# 2_bootleg-alps-matrix.net
KiCad netlist of a schematic drawn in Altium Designer
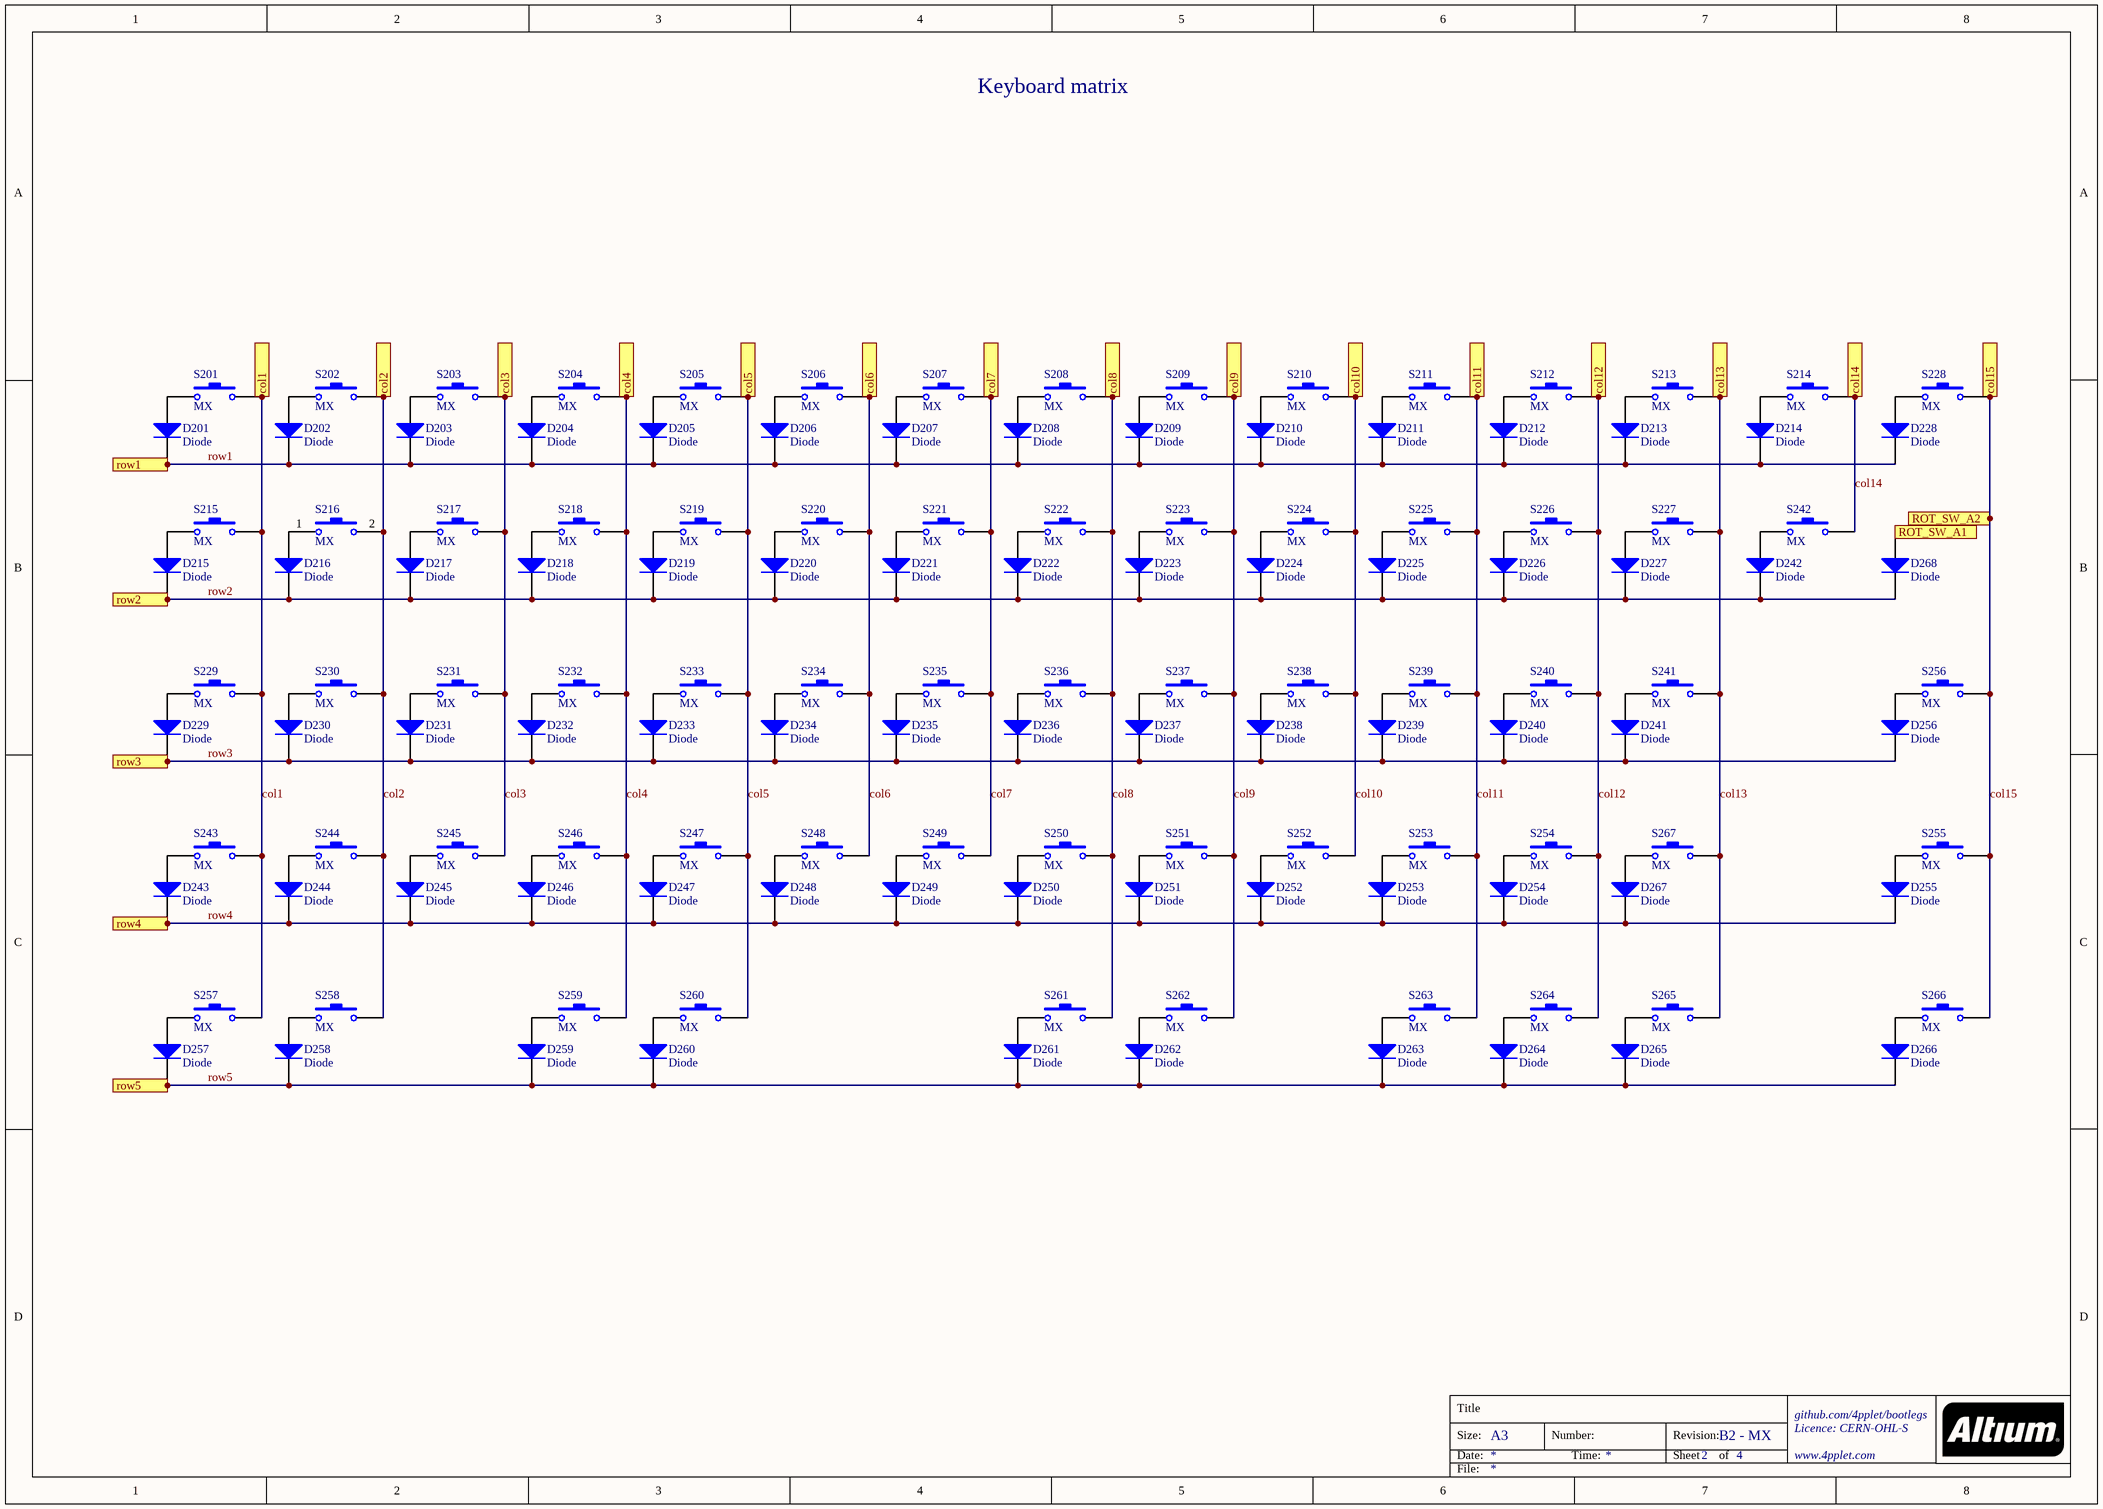
[diagram p0: 2_bootleg-alps-matrix.SchDoc]

(export (version "E")
  (design (tool "Eeschema 10.0.6"))
  (components
    (comp (ref "D201")
      (value "Diode")
      (footprint "SOD-123")
      (description "Default Diode")
      (fields (field (name "LCSC PART #") "C81598") (field (name "MRF.PART") "1N4148W"))
      (libsource (lib "Miscellaneous Devices") (part "Diode"))
    )
    (comp (ref "D202")
      (value "Diode")
      (footprint "SOD-123")
      (description "Default Diode")
      (fields (field (name "LCSC PART #") "C81598") (field (name "MRF.PART") "1N4148W"))
      (libsource (lib "Miscellaneous Devices") (part "Diode"))
    )
    (comp (ref "D203")
      (value "Diode")
      (footprint "SOD-123")
      (description "Default Diode")
      (fields (field (name "LCSC PART #") "C81598") (field (name "MRF.PART") "1N4148W"))
      (libsource (lib "Miscellaneous Devices") (part "Diode"))
    )
    (comp (ref "D204")
      (value "Diode")
      (footprint "SOD-123")
      (description "Default Diode")
      (fields (field (name "LCSC PART #") "C81598") (field (name "MRF.PART") "1N4148W"))
      (libsource (lib "Miscellaneous Devices") (part "Diode"))
    )
    (comp (ref "D205")
      (value "Diode")
      (footprint "SOD-123")
      (description "Default Diode")
      (fields (field (name "LCSC PART #") "C81598") (field (name "MRF.PART") "1N4148W"))
      (libsource (lib "Miscellaneous Devices") (part "Diode"))
    )
    (comp (ref "D206")
      (value "Diode")
      (footprint "SOD-123")
      (description "Default Diode")
      (fields (field (name "LCSC PART #") "C81598") (field (name "MRF.PART") "1N4148W"))
      (libsource (lib "Miscellaneous Devices") (part "Diode"))
    )
    (comp (ref "D207")
      (value "Diode")
      (footprint "SOD-123")
      (description "Default Diode")
      (fields (field (name "LCSC PART #") "C81598") (field (name "MRF.PART") "1N4148W"))
      (libsource (lib "Miscellaneous Devices") (part "Diode"))
    )
    (comp (ref "D208")
      (value "Diode")
      (footprint "SOD-123")
      (description "Default Diode")
      (fields (field (name "LCSC PART #") "C81598") (field (name "MRF.PART") "1N4148W"))
      (libsource (lib "Miscellaneous Devices") (part "Diode"))
    )
    (comp (ref "D209")
      (value "Diode")
      (footprint "SOD-123")
      (description "Default Diode")
      (fields (field (name "LCSC PART #") "C81598") (field (name "MRF.PART") "1N4148W"))
      (libsource (lib "Miscellaneous Devices") (part "Diode"))
    )
    (comp (ref "D210")
      (value "Diode")
      (footprint "SOD-123")
      (description "Default Diode")
      (fields (field (name "LCSC PART #") "C81598") (field (name "MRF.PART") "1N4148W"))
      (libsource (lib "Miscellaneous Devices") (part "Diode"))
    )
    (comp (ref "D211")
      (value "Diode")
      (footprint "SOD-123")
      (description "Default Diode")
      (fields (field (name "LCSC PART #") "C81598") (field (name "MRF.PART") "1N4148W"))
      (libsource (lib "Miscellaneous Devices") (part "Diode"))
    )
    (comp (ref "D212")
      (value "Diode")
      (footprint "SOD-123")
      (description "Default Diode")
      (fields (field (name "LCSC PART #") "C81598") (field (name "MRF.PART") "1N4148W"))
      (libsource (lib "Miscellaneous Devices") (part "Diode"))
    )
    (comp (ref "D213")
      (value "Diode")
      (footprint "SOD-123")
      (description "Default Diode")
      (fields (field (name "LCSC PART #") "C81598") (field (name "MRF.PART") "1N4148W"))
      (libsource (lib "Miscellaneous Devices") (part "Diode"))
    )
    (comp (ref "D214")
      (value "Diode")
      (footprint "SOD-123")
      (description "Default Diode")
      (fields (field (name "LCSC PART #") "C81598") (field (name "MRF.PART") "1N4148W"))
      (libsource (lib "Miscellaneous Devices") (part "Diode"))
    )
    (comp (ref "D215")
      (value "Diode")
      (footprint "SOD-123")
      (description "Default Diode")
      (fields (field (name "LCSC PART #") "C81598") (field (name "MRF.PART") "1N4148W"))
      (libsource (lib "Miscellaneous Devices") (part "Diode"))
    )
    (comp (ref "D216")
      (value "Diode")
      (footprint "SOD-123")
      (description "Default Diode")
      (fields (field (name "LCSC PART #") "C81598") (field (name "MRF.PART") "1N4148W"))
      (libsource (lib "Miscellaneous Devices") (part "Diode"))
    )
    (comp (ref "D217")
      (value "Diode")
      (footprint "SOD-123")
      (description "Default Diode")
      (fields (field (name "LCSC PART #") "C81598") (field (name "MRF.PART") "1N4148W"))
      (libsource (lib "Miscellaneous Devices") (part "Diode"))
    )
    (comp (ref "D218")
      (value "Diode")
      (footprint "SOD-123")
      (description "Default Diode")
      (fields (field (name "LCSC PART #") "C81598") (field (name "MRF.PART") "1N4148W"))
      (libsource (lib "Miscellaneous Devices") (part "Diode"))
    )
    (comp (ref "D219")
      (value "Diode")
      (footprint "SOD-123")
      (description "Default Diode")
      (fields (field (name "LCSC PART #") "C81598") (field (name "MRF.PART") "1N4148W"))
      (libsource (lib "Miscellaneous Devices") (part "Diode"))
    )
    (comp (ref "D220")
      (value "Diode")
      (footprint "SOD-123")
      (description "Default Diode")
      (fields (field (name "LCSC PART #") "C81598") (field (name "MRF.PART") "1N4148W"))
      (libsource (lib "Miscellaneous Devices") (part "Diode"))
    )
    (comp (ref "D221")
      (value "Diode")
      (footprint "SOD-123")
      (description "Default Diode")
      (fields (field (name "LCSC PART #") "C81598") (field (name "MRF.PART") "1N4148W"))
      (libsource (lib "Miscellaneous Devices") (part "Diode"))
    )
    (comp (ref "D222")
      (value "Diode")
      (footprint "SOD-123")
      (description "Default Diode")
      (fields (field (name "LCSC PART #") "C81598") (field (name "MRF.PART") "1N4148W"))
      (libsource (lib "Miscellaneous Devices") (part "Diode"))
    )
    (comp (ref "D223")
      (value "Diode")
      (footprint "SOD-123")
      (description "Default Diode")
      (fields (field (name "LCSC PART #") "C81598") (field (name "MRF.PART") "1N4148W"))
      (libsource (lib "Miscellaneous Devices") (part "Diode"))
    )
    (comp (ref "D224")
      (value "Diode")
      (footprint "SOD-123")
      (description "Default Diode")
      (fields (field (name "LCSC PART #") "C81598") (field (name "MRF.PART") "1N4148W"))
      (libsource (lib "Miscellaneous Devices") (part "Diode"))
    )
    (comp (ref "D225")
      (value "Diode")
      (footprint "SOD-123")
      (description "Default Diode")
      (fields (field (name "LCSC PART #") "C81598") (field (name "MRF.PART") "1N4148W"))
      (libsource (lib "Miscellaneous Devices") (part "Diode"))
    )
    (comp (ref "D226")
      (value "Diode")
      (footprint "SOD-123")
      (description "Default Diode")
      (fields (field (name "LCSC PART #") "C81598") (field (name "MRF.PART") "1N4148W"))
      (libsource (lib "Miscellaneous Devices") (part "Diode"))
    )
    (comp (ref "D227")
      (value "Diode")
      (footprint "SOD-123")
      (description "Default Diode")
      (fields (field (name "LCSC PART #") "C81598") (field (name "MRF.PART") "1N4148W"))
      (libsource (lib "Miscellaneous Devices") (part "Diode"))
    )
    (comp (ref "D228")
      (value "Diode")
      (footprint "SOD-123")
      (description "Default Diode")
      (fields (field (name "LCSC PART #") "C81598") (field (name "MRF.PART") "1N4148W"))
      (libsource (lib "Miscellaneous Devices") (part "Diode"))
    )
    (comp (ref "D229")
      (value "Diode")
      (footprint "SOD-123")
      (description "Default Diode")
      (fields (field (name "LCSC PART #") "C81598") (field (name "MRF.PART") "1N4148W"))
      (libsource (lib "Miscellaneous Devices") (part "Diode"))
    )
    (comp (ref "D230")
      (value "Diode")
      (footprint "SOD-123")
      (description "Default Diode")
      (fields (field (name "LCSC PART #") "C81598") (field (name "MRF.PART") "1N4148W"))
      (libsource (lib "Miscellaneous Devices") (part "Diode"))
    )
    (comp (ref "D231")
      (value "Diode")
      (footprint "SOD-123")
      (description "Default Diode")
      (fields (field (name "LCSC PART #") "C81598") (field (name "MRF.PART") "1N4148W"))
      (libsource (lib "Miscellaneous Devices") (part "Diode"))
    )
    (comp (ref "D232")
      (value "Diode")
      (footprint "SOD-123")
      (description "Default Diode")
      (fields (field (name "LCSC PART #") "C81598") (field (name "MRF.PART") "1N4148W"))
      (libsource (lib "Miscellaneous Devices") (part "Diode"))
    )
    (comp (ref "D233")
      (value "Diode")
      (footprint "SOD-123")
      (description "Default Diode")
      (fields (field (name "LCSC PART #") "C81598") (field (name "MRF.PART") "1N4148W"))
      (libsource (lib "Miscellaneous Devices") (part "Diode"))
    )
    (comp (ref "D234")
      (value "Diode")
      (footprint "SOD-123")
      (description "Default Diode")
      (fields (field (name "LCSC PART #") "C81598") (field (name "MRF.PART") "1N4148W"))
      (libsource (lib "Miscellaneous Devices") (part "Diode"))
    )
    (comp (ref "D235")
      (value "Diode")
      (footprint "SOD-123")
      (description "Default Diode")
      (fields (field (name "LCSC PART #") "C81598") (field (name "MRF.PART") "1N4148W"))
      (libsource (lib "Miscellaneous Devices") (part "Diode"))
    )
    (comp (ref "D236")
      (value "Diode")
      (footprint "SOD-123")
      (description "Default Diode")
      (fields (field (name "LCSC PART #") "C81598") (field (name "MRF.PART") "1N4148W"))
      (libsource (lib "Miscellaneous Devices") (part "Diode"))
    )
    (comp (ref "D237")
      (value "Diode")
      (footprint "SOD-123")
      (description "Default Diode")
      (fields (field (name "LCSC PART #") "C81598") (field (name "MRF.PART") "1N4148W"))
      (libsource (lib "Miscellaneous Devices") (part "Diode"))
    )
    (comp (ref "D238")
      (value "Diode")
      (footprint "SOD-123")
      (description "Default Diode")
      (fields (field (name "LCSC PART #") "C81598") (field (name "MRF.PART") "1N4148W"))
      (libsource (lib "Miscellaneous Devices") (part "Diode"))
    )
    (comp (ref "D239")
      (value "Diode")
      (footprint "SOD-123")
      (description "Default Diode")
      (fields (field (name "LCSC PART #") "C81598") (field (name "MRF.PART") "1N4148W"))
      (libsource (lib "Miscellaneous Devices") (part "Diode"))
    )
    (comp (ref "D240")
      (value "Diode")
      (footprint "SOD-123")
      (description "Default Diode")
      (fields (field (name "LCSC PART #") "C81598") (field (name "MRF.PART") "1N4148W"))
      (libsource (lib "Miscellaneous Devices") (part "Diode"))
    )
    (comp (ref "D241")
      (value "Diode")
      (footprint "SOD-123")
      (description "Default Diode")
      (fields (field (name "LCSC PART #") "C81598") (field (name "MRF.PART") "1N4148W"))
      (libsource (lib "Miscellaneous Devices") (part "Diode"))
    )
    (comp (ref "D242")
      (value "Diode")
      (footprint "SOD-123")
      (description "Default Diode")
      (fields (field (name "LCSC PART #") "C81598") (field (name "MRF.PART") "1N4148W"))
      (libsource (lib "Miscellaneous Devices") (part "Diode"))
    )
    (comp (ref "D243")
      (value "Diode")
      (footprint "SOD-123")
      (description "Default Diode")
      (fields (field (name "LCSC PART #") "C81598") (field (name "MRF.PART") "1N4148W"))
      (libsource (lib "Miscellaneous Devices") (part "Diode"))
    )
    (comp (ref "D244")
      (value "Diode")
      (footprint "SOD-123")
      (description "Default Diode")
      (fields (field (name "LCSC PART #") "C81598") (field (name "MRF.PART") "1N4148W"))
      (libsource (lib "Miscellaneous Devices") (part "Diode"))
    )
    (comp (ref "D245")
      (value "Diode")
      (footprint "SOD-123")
      (description "Default Diode")
      (fields (field (name "LCSC PART #") "C81598") (field (name "MRF.PART") "1N4148W"))
      (libsource (lib "Miscellaneous Devices") (part "Diode"))
    )
    (comp (ref "D246")
      (value "Diode")
      (footprint "SOD-123")
      (description "Default Diode")
      (fields (field (name "LCSC PART #") "C81598") (field (name "MRF.PART") "1N4148W"))
      (libsource (lib "Miscellaneous Devices") (part "Diode"))
    )
    (comp (ref "D247")
      (value "Diode")
      (footprint "SOD-123")
      (description "Default Diode")
      (fields (field (name "LCSC PART #") "C81598") (field (name "MRF.PART") "1N4148W"))
      (libsource (lib "Miscellaneous Devices") (part "Diode"))
    )
    (comp (ref "D248")
      (value "Diode")
      (footprint "SOD-123")
      (description "Default Diode")
      (fields (field (name "LCSC PART #") "C81598") (field (name "MRF.PART") "1N4148W"))
      (libsource (lib "Miscellaneous Devices") (part "Diode"))
    )
    (comp (ref "D249")
      (value "Diode")
      (footprint "SOD-123")
      (description "Default Diode")
      (fields (field (name "LCSC PART #") "C81598") (field (name "MRF.PART") "1N4148W"))
      (libsource (lib "Miscellaneous Devices") (part "Diode"))
    )
    (comp (ref "D250")
      (value "Diode")
      (footprint "SOD-123")
      (description "Default Diode")
      (fields (field (name "LCSC PART #") "C81598") (field (name "MRF.PART") "1N4148W"))
      (libsource (lib "Miscellaneous Devices") (part "Diode"))
    )
    (comp (ref "D251")
      (value "Diode")
      (footprint "SOD-123")
      (description "Default Diode")
      (fields (field (name "LCSC PART #") "C81598") (field (name "MRF.PART") "1N4148W"))
      (libsource (lib "Miscellaneous Devices") (part "Diode"))
    )
    (comp (ref "D252")
      (value "Diode")
      (footprint "SOD-123")
      (description "Default Diode")
      (fields (field (name "LCSC PART #") "C81598") (field (name "MRF.PART") "1N4148W"))
      (libsource (lib "Miscellaneous Devices") (part "Diode"))
    )
    (comp (ref "D253")
      (value "Diode")
      (footprint "SOD-123")
      (description "Default Diode")
      (fields (field (name "LCSC PART #") "C81598") (field (name "MRF.PART") "1N4148W"))
      (libsource (lib "Miscellaneous Devices") (part "Diode"))
    )
    (comp (ref "D254")
      (value "Diode")
      (footprint "SOD-123")
      (description "Default Diode")
      (fields (field (name "LCSC PART #") "C81598") (field (name "MRF.PART") "1N4148W"))
      (libsource (lib "Miscellaneous Devices") (part "Diode"))
    )
    (comp (ref "D255")
      (value "Diode")
      (footprint "SOD-123")
      (description "Default Diode")
      (fields (field (name "LCSC PART #") "C81598") (field (name "MRF.PART") "1N4148W"))
      (libsource (lib "Miscellaneous Devices") (part "Diode"))
    )
    (comp (ref "D256")
      (value "Diode")
      (footprint "SOD-123")
      (description "Default Diode")
      (fields (field (name "LCSC PART #") "C81598") (field (name "MRF.PART") "1N4148W"))
      (libsource (lib "Miscellaneous Devices") (part "Diode"))
    )
    (comp (ref "D257")
      (value "Diode")
      (footprint "SOD-123")
      (description "Default Diode")
      (fields (field (name "LCSC PART #") "C81598") (field (name "MRF.PART") "1N4148W"))
      (libsource (lib "Miscellaneous Devices") (part "Diode"))
    )
    (comp (ref "D258")
      (value "Diode")
      (footprint "SOD-123")
      (description "Default Diode")
      (fields (field (name "LCSC PART #") "C81598") (field (name "MRF.PART") "1N4148W"))
      (libsource (lib "Miscellaneous Devices") (part "Diode"))
    )
    (comp (ref "D259")
      (value "Diode")
      (footprint "SOD-123")
      (description "Default Diode")
      (fields (field (name "LCSC PART #") "C81598") (field (name "MRF.PART") "1N4148W"))
      (libsource (lib "Miscellaneous Devices") (part "Diode"))
    )
    (comp (ref "D260")
      (value "Diode")
      (footprint "SOD-123")
      (description "Default Diode")
      (fields (field (name "LCSC PART #") "C81598") (field (name "MRF.PART") "1N4148W"))
      (libsource (lib "Miscellaneous Devices") (part "Diode"))
    )
    (comp (ref "D261")
      (value "Diode")
      (footprint "SOD-123")
      (description "Default Diode")
      (fields (field (name "LCSC PART #") "C81598") (field (name "MRF.PART") "1N4148W"))
      (libsource (lib "Miscellaneous Devices") (part "Diode"))
    )
    (comp (ref "D262")
      (value "Diode")
      (footprint "SOD-123")
      (description "Default Diode")
      (fields (field (name "LCSC PART #") "C81598") (field (name "MRF.PART") "1N4148W"))
      (libsource (lib "Miscellaneous Devices") (part "Diode"))
    )
    (comp (ref "D263")
      (value "Diode")
      (footprint "SOD-123")
      (description "Default Diode")
      (fields (field (name "LCSC PART #") "C81598") (field (name "MRF.PART") "1N4148W"))
      (libsource (lib "Miscellaneous Devices") (part "Diode"))
    )
    (comp (ref "D264")
      (value "Diode")
      (footprint "SOD-123")
      (description "Default Diode")
      (fields (field (name "LCSC PART #") "C81598") (field (name "MRF.PART") "1N4148W"))
      (libsource (lib "Miscellaneous Devices") (part "Diode"))
    )
    (comp (ref "D265")
      (value "Diode")
      (footprint "SOD-123")
      (description "Default Diode")
      (fields (field (name "LCSC PART #") "C81598") (field (name "MRF.PART") "1N4148W"))
      (libsource (lib "Miscellaneous Devices") (part "Diode"))
    )
    (comp (ref "D266")
      (value "Diode")
      (footprint "SOD-123")
      (description "Default Diode")
      (fields (field (name "LCSC PART #") "C81598") (field (name "MRF.PART") "1N4148W"))
      (libsource (lib "Miscellaneous Devices") (part "Diode"))
    )
    (comp (ref "D267")
      (value "Diode")
      (footprint "SOD-123")
      (description "Default Diode")
      (fields (field (name "LCSC PART #") "C81598") (field (name "MRF.PART") "1N4148W"))
      (libsource (lib "Miscellaneous Devices") (part "Diode"))
    )
    (comp (ref "D268")
      (value "Diode")
      (footprint "SOD-123")
      (description "Default Diode")
      (fields (field (name "LCSC PART #") "C81598") (field (name "MRF.PART") "1N4148W"))
      (libsource (lib "Miscellaneous Devices") (part "Diode"))
    )
    (comp (ref "S201")
      (value "MX")
      (footprint "Alps-switch - switched pol")
      (description "Switch")
      (libsource (lib "Miscellaneous Devices") (part "SW-PB"))
    )
    (comp (ref "S202")
      (value "MX")
      (footprint "Alps-switch")
      (description "Switch")
      (libsource (lib "Miscellaneous Devices") (part "SW-PB"))
    )
    (comp (ref "S203")
      (value "MX")
      (footprint "Alps-switch - switched pol")
      (description "Switch")
      (libsource (lib "Miscellaneous Devices") (part "SW-PB"))
    )
    (comp (ref "S204")
      (value "MX")
      (footprint "Alps-switch - switched pol")
      (description "Switch")
      (libsource (lib "Miscellaneous Devices") (part "SW-PB"))
    )
    (comp (ref "S205")
      (value "MX")
      (footprint "Alps-switch - switched pol")
      (description "Switch")
      (libsource (lib "Miscellaneous Devices") (part "SW-PB"))
    )
    (comp (ref "S206")
      (value "MX")
      (footprint "Alps-switch - switched pol")
      (description "Switch")
      (libsource (lib "Miscellaneous Devices") (part "SW-PB"))
    )
    (comp (ref "S207")
      (value "MX")
      (footprint "Alps-switch - switched pol")
      (description "Switch")
      (libsource (lib "Miscellaneous Devices") (part "SW-PB"))
    )
    (comp (ref "S208")
      (value "MX")
      (footprint "Alps-switch - switched pol")
      (description "Switch")
      (libsource (lib "Miscellaneous Devices") (part "SW-PB"))
    )
    (comp (ref "S209")
      (value "MX")
      (footprint "Alps-switch - switched pol")
      (description "Switch")
      (libsource (lib "Miscellaneous Devices") (part "SW-PB"))
    )
    (comp (ref "S210")
      (value "MX")
      (footprint "Alps-switch - switched pol")
      (description "Switch")
      (libsource (lib "Miscellaneous Devices") (part "SW-PB"))
    )
    (comp (ref "S211")
      (value "MX")
      (footprint "Alps-switch - switched pol")
      (description "Switch")
      (libsource (lib "Miscellaneous Devices") (part "SW-PB"))
    )
    (comp (ref "S212")
      (value "MX")
      (footprint "Alps-switch - switched pol")
      (description "Switch")
      (libsource (lib "Miscellaneous Devices") (part "SW-PB"))
    )
    (comp (ref "S213")
      (value "MX")
      (footprint "Alps-switch - switched pol")
      (description "Switch")
      (libsource (lib "Miscellaneous Devices") (part "SW-PB"))
    )
    (comp (ref "S214")
      (value "MX")
      (footprint "Alps-switch - switched pol")
      (description "Switch")
      (libsource (lib "Miscellaneous Devices") (part "SW-PB"))
    )
    (comp (ref "S215")
      (value "MX")
      (footprint "ALPS-switch - 1.5U")
      (description "TAB")
      (libsource (lib "Miscellaneous Devices") (part "SW-PB"))
    )
    (comp (ref "S216")
      (value "MX")
      (footprint "Alps-switch - switched pol")
      (description "Switch")
      (libsource (lib "") (part "SW-PB_1"))
    )
    (comp (ref "S217")
      (value "MX")
      (footprint "Alps-switch - switched pol")
      (description "Switch")
      (libsource (lib "Miscellaneous Devices") (part "SW-PB"))
    )
    (comp (ref "S218")
      (value "MX")
      (footprint "Alps-switch - switched pol")
      (description "Switch")
      (libsource (lib "Miscellaneous Devices") (part "SW-PB"))
    )
    (comp (ref "S219")
      (value "MX")
      (footprint "Alps-switch - switched pol")
      (description "Switch")
      (libsource (lib "Miscellaneous Devices") (part "SW-PB"))
    )
    (comp (ref "S220")
      (value "MX")
      (footprint "Alps-switch - switched pol")
      (description "Switch")
      (libsource (lib "Miscellaneous Devices") (part "SW-PB"))
    )
    (comp (ref "S221")
      (value "MX")
      (footprint "Alps-switch - switched pol")
      (description "Switch")
      (libsource (lib "Miscellaneous Devices") (part "SW-PB"))
    )
    (comp (ref "S222")
      (value "MX")
      (footprint "Alps-switch - switched pol")
      (description "Switch")
      (libsource (lib "Miscellaneous Devices") (part "SW-PB"))
    )
    (comp (ref "S223")
      (value "MX")
      (footprint "Alps-switch - switched pol")
      (description "Switch")
      (libsource (lib "Miscellaneous Devices") (part "SW-PB"))
    )
    (comp (ref "S224")
      (value "MX")
      (footprint "Alps-switch - switched pol")
      (description "Switch")
      (libsource (lib "Miscellaneous Devices") (part "SW-PB"))
    )
    (comp (ref "S225")
      (value "MX")
      (footprint "Alps-switch - switched pol")
      (description "Switch")
      (libsource (lib "Miscellaneous Devices") (part "SW-PB"))
    )
    (comp (ref "S226")
      (value "MX")
      (footprint "Alps-switch")
      (description "Switch")
      (libsource (lib "Miscellaneous Devices") (part "SW-PB"))
    )
    (comp (ref "S227")
      (value "MX")
      (footprint "Alps-switch - switched pol")
      (description "Switch")
      (libsource (lib "Miscellaneous Devices") (part "SW-PB"))
    )
    (comp (ref "S228")
      (value "MX")
      (footprint "ALPS-switch - backspace")
      (description "Switch")
      (libsource (lib "Miscellaneous Devices") (part "SW-PB"))
    )
    (comp (ref "S229")
      (value "MX")
      (footprint "ALPS-switch - CAPS")
      (description "Switch")
      (libsource (lib "Miscellaneous Devices") (part "SW-PB"))
    )
    (comp (ref "S230")
      (value "MX")
      (footprint "Alps-switch - switched pol")
      (description "Switch")
      (libsource (lib "Miscellaneous Devices") (part "SW-PB"))
    )
    (comp (ref "S231")
      (value "MX")
      (footprint "Alps-switch - switched pol")
      (description "Switch")
      (libsource (lib "Miscellaneous Devices") (part "SW-PB"))
    )
    (comp (ref "S232")
      (value "MX")
      (footprint "Alps-switch - switched pol")
      (description "Switch")
      (libsource (lib "Miscellaneous Devices") (part "SW-PB"))
    )
    (comp (ref "S233")
      (value "MX")
      (footprint "Alps-switch - switched pol")
      (description "Switch")
      (libsource (lib "Miscellaneous Devices") (part "SW-PB"))
    )
    (comp (ref "S234")
      (value "MX")
      (footprint "Alps-switch - switched pol")
      (description "Switch")
      (libsource (lib "Miscellaneous Devices") (part "SW-PB"))
    )
    (comp (ref "S235")
      (value "MX")
      (footprint "Alps-switch - switched pol")
      (description "Switch")
      (libsource (lib "Miscellaneous Devices") (part "SW-PB"))
    )
    (comp (ref "S236")
      (value "MX")
      (footprint "Alps-switch - switched pol")
      (description "Switch")
      (libsource (lib "Miscellaneous Devices") (part "SW-PB"))
    )
    (comp (ref "S237")
      (value "MX")
      (footprint "Alps-switch - switched pol")
      (description "Switch")
      (libsource (lib "Miscellaneous Devices") (part "SW-PB"))
    )
    (comp (ref "S238")
      (value "MX")
      (footprint "Alps-switch - switched pol")
      (description "Switch")
      (libsource (lib "Miscellaneous Devices") (part "SW-PB"))
    )
    (comp (ref "S239")
      (value "MX")
      (footprint "Alps-switch")
      (description "Switch")
      (libsource (lib "Miscellaneous Devices") (part "SW-PB"))
    )
    (comp (ref "S240")
      (value "MX")
      (footprint "Alps-switch - switched pol")
      (description "Switch")
      (libsource (lib "Miscellaneous Devices") (part "SW-PB"))
    )
    (comp (ref "S241")
      (value "MX")
      (footprint "Alps-switch")
      (description "Switch")
      (libsource (lib "Miscellaneous Devices") (part "SW-PB"))
    )
    (comp (ref "S242")
      (value "MX")
      (footprint "ALPS-switch - 1.5U")
      (description "Switch")
      (libsource (lib "Miscellaneous Devices") (part "SW-PB"))
    )
    (comp (ref "S243")
      (value "MX")
      (footprint "ALPS-switch - Left shift v2")
      (description "Switch")
      (libsource (lib "Miscellaneous Devices") (part "SW-PB"))
    )
    (comp (ref "S244")
      (value "MX")
      (footprint "Alps-switch")
      (description "Switch")
      (libsource (lib "Miscellaneous Devices") (part "SW-PB"))
    )
    (comp (ref "S245")
      (value "MX")
      (footprint "Alps-switch - switched pol")
      (description "Switch")
      (libsource (lib "Miscellaneous Devices") (part "SW-PB"))
    )
    (comp (ref "S246")
      (value "MX")
      (footprint "Alps-switch - switched pol")
      (description "Switch")
      (libsource (lib "Miscellaneous Devices") (part "SW-PB"))
    )
    (comp (ref "S247")
      (value "MX")
      (footprint "Alps-switch - switched pol")
      (description "Switch")
      (libsource (lib "Miscellaneous Devices") (part "SW-PB"))
    )
    (comp (ref "S248")
      (value "MX")
      (footprint "Alps-switch - switched pol")
      (description "Switch")
      (libsource (lib "Miscellaneous Devices") (part "SW-PB"))
    )
    (comp (ref "S249")
      (value "MX")
      (footprint "Alps-switch - switched pol")
      (description "Switch")
      (libsource (lib "Miscellaneous Devices") (part "SW-PB"))
    )
    (comp (ref "S250")
      (value "MX")
      (footprint "Alps-switch - switched pol")
      (description "Switch")
      (libsource (lib "Miscellaneous Devices") (part "SW-PB"))
    )
    (comp (ref "S251")
      (value "MX")
      (footprint "Alps-switch - switched pol")
      (description "Switch")
      (libsource (lib "Miscellaneous Devices") (part "SW-PB"))
    )
    (comp (ref "S252")
      (value "MX")
      (footprint "Alps-switch - switched pol")
      (description "Switch")
      (libsource (lib "Miscellaneous Devices") (part "SW-PB"))
    )
    (comp (ref "S253")
      (value "MX")
      (footprint "Alps-switch - switched pol")
      (description "Switch")
      (libsource (lib "Miscellaneous Devices") (part "SW-PB"))
    )
    (comp (ref "S254")
      (value "MX")
      (footprint "Alps-switch - switched pol")
      (description "Switch")
      (libsource (lib "Miscellaneous Devices") (part "SW-PB"))
    )
    (comp (ref "S255")
      (value "MX")
      (footprint "Alps-switch")
      (description "Switch")
      (libsource (lib "Miscellaneous Devices") (part "SW-PB"))
    )
    (comp (ref "S256")
      (value "MX")
      (footprint "ALPS-switch - Enter - rotated stab")
      (description "Switch")
      (libsource (lib "Miscellaneous Devices") (part "SW-PB"))
    )
    (comp (ref "S257")
      (value "MX")
      (footprint "ALPS-switch - 1.5u MOD-L")
      (description "Switch")
      (libsource (lib "Miscellaneous Devices") (part "SW-PB"))
    )
    (comp (ref "S258")
      (value "MX")
      (footprint "ALPS-switch - 1.5u MOD-L")
      (description "Switch")
      (libsource (lib "Miscellaneous Devices") (part "SW-PB"))
    )
    (comp (ref "S259")
      (value "MX")
      (footprint "ALPS-switch - 1.5u MOD-L")
      (description "Switch")
      (libsource (lib "Miscellaneous Devices") (part "SW-PB"))
    )
    (comp (ref "S260")
      (value "MX")
      (footprint "ALPS-switch - L split space_V3")
      (description "Switch")
      (libsource (lib "Miscellaneous Devices") (part "SW-PB"))
    )
    (comp (ref "S261")
      (value "MX")
      (footprint "ALPS-switch - Space_V3")
      (description "Switch")
      (libsource (lib "Miscellaneous Devices") (part "SW-PB"))
    )
    (comp (ref "S262")
      (value "MX")
      (footprint "ALPS-switch - R split space_V3")
      (description "Switch")
      (libsource (lib "Miscellaneous Devices") (part "SW-PB"))
    )
    (comp (ref "S263")
      (value "MX")
      (footprint "Alps-switch")
      (description "Switch")
      (libsource (lib "Miscellaneous Devices") (part "SW-PB"))
    )
    (comp (ref "S264")
      (value "MX")
      (footprint "ALPS-switch - 1.5u MOD-R")
      (description "Switch")
      (libsource (lib "Miscellaneous Devices") (part "SW-PB"))
    )
    (comp (ref "S265")
      (value "MX")
      (footprint "ALPS-switch - 1.5u MOD-R")
      (description "Switch")
      (libsource (lib "Miscellaneous Devices") (part "SW-PB"))
    )
    (comp (ref "S266")
      (value "MX")
      (footprint "ALPS-switch - 1.5u MOD-R")
      (description "Switch")
      (libsource (lib "Miscellaneous Devices") (part "SW-PB"))
    )
    (comp (ref "S267")
      (value "MX")
      (footprint "ALPS-switch - right shift - stabs")
      (description "Switch")
      (libsource (lib "Miscellaneous Devices") (part "SW-PB"))
    )
  )
  (nets
    (net (code "1") (name "/ROT_SW_A1") (class "Default")
      (node (ref "D268") (pin "1") (pinfunction "A_1") (pintype "passive"))
    )
    (net (code "2") (name "/col1") (class "Default")
      (node (ref "S201") (pin "2") (pinfunction "2_2") (pintype "passive"))
      (node (ref "S215") (pin "1") (pinfunction "1_1") (pintype "passive"))
      (node (ref "S229") (pin "2") (pinfunction "2_2") (pintype "passive"))
      (node (ref "S243") (pin "2") (pinfunction "2_2") (pintype "passive"))
      (node (ref "S257") (pin "1") (pinfunction "1_1") (pintype "passive"))
    )
    (net (code "3") (name "/col2") (class "Default")
      (node (ref "S202") (pin "2") (pinfunction "2_2") (pintype "passive"))
      (node (ref "S216") (pin "2") (pinfunction "2_2") (pintype "passive"))
      (node (ref "S230") (pin "2") (pinfunction "2_2") (pintype "passive"))
      (node (ref "S244") (pin "2") (pinfunction "2_2") (pintype "passive"))
      (node (ref "S258") (pin "2") (pinfunction "2_2") (pintype "passive"))
    )
    (net (code "4") (name "/col3") (class "Default")
      (node (ref "S203") (pin "2") (pinfunction "2_2") (pintype "passive"))
      (node (ref "S217") (pin "2") (pinfunction "2_2") (pintype "passive"))
      (node (ref "S231") (pin "2") (pinfunction "2_2") (pintype "passive"))
      (node (ref "S245") (pin "2") (pinfunction "2_2") (pintype "passive"))
    )
    (net (code "5") (name "/col4") (class "Default")
      (node (ref "S204") (pin "2") (pinfunction "2_2") (pintype "passive"))
      (node (ref "S218") (pin "2") (pinfunction "2_2") (pintype "passive"))
      (node (ref "S232") (pin "2") (pinfunction "2_2") (pintype "passive"))
      (node (ref "S246") (pin "2") (pinfunction "2_2") (pintype "passive"))
      (node (ref "S259") (pin "2") (pinfunction "2_2") (pintype "passive"))
    )
    (net (code "6") (name "/col5") (class "Default")
      (node (ref "S205") (pin "2") (pinfunction "2_2") (pintype "passive"))
      (node (ref "S219") (pin "2") (pinfunction "2_2") (pintype "passive"))
      (node (ref "S233") (pin "2") (pinfunction "2_2") (pintype "passive"))
      (node (ref "S247") (pin "2") (pinfunction "2_2") (pintype "passive"))
      (node (ref "S260") (pin "2") (pinfunction "2_2") (pintype "passive"))
    )
    (net (code "7") (name "/col6") (class "Default")
      (node (ref "S206") (pin "2") (pinfunction "2_2") (pintype "passive"))
      (node (ref "S220") (pin "2") (pinfunction "2_2") (pintype "passive"))
      (node (ref "S234") (pin "2") (pinfunction "2_2") (pintype "passive"))
      (node (ref "S248") (pin "2") (pinfunction "2_2") (pintype "passive"))
    )
    (net (code "8") (name "/col7") (class "Default")
      (node (ref "S207") (pin "2") (pinfunction "2_2") (pintype "passive"))
      (node (ref "S221") (pin "2") (pinfunction "2_2") (pintype "passive"))
      (node (ref "S235") (pin "2") (pinfunction "2_2") (pintype "passive"))
      (node (ref "S249") (pin "2") (pinfunction "2_2") (pintype "passive"))
    )
    (net (code "9") (name "/col8") (class "Default")
      (node (ref "S208") (pin "2") (pinfunction "2_2") (pintype "passive"))
      (node (ref "S222") (pin "2") (pinfunction "2_2") (pintype "passive"))
      (node (ref "S236") (pin "2") (pinfunction "2_2") (pintype "passive"))
      (node (ref "S250") (pin "2") (pinfunction "2_2") (pintype "passive"))
      (node (ref "S261") (pin "2") (pinfunction "2_2") (pintype "passive"))
    )
    (net (code "10") (name "/col9") (class "Default")
      (node (ref "S209") (pin "2") (pinfunction "2_2") (pintype "passive"))
      (node (ref "S223") (pin "2") (pinfunction "2_2") (pintype "passive"))
      (node (ref "S237") (pin "2") (pinfunction "2_2") (pintype "passive"))
      (node (ref "S251") (pin "2") (pinfunction "2_2") (pintype "passive"))
      (node (ref "S262") (pin "2") (pinfunction "2_2") (pintype "passive"))
    )
    (net (code "11") (name "/col10") (class "Default")
      (node (ref "S210") (pin "2") (pinfunction "2_2") (pintype "passive"))
      (node (ref "S224") (pin "2") (pinfunction "2_2") (pintype "passive"))
      (node (ref "S238") (pin "2") (pinfunction "2_2") (pintype "passive"))
      (node (ref "S252") (pin "2") (pinfunction "2_2") (pintype "passive"))
    )
    (net (code "12") (name "/col11") (class "Default")
      (node (ref "S211") (pin "2") (pinfunction "2_2") (pintype "passive"))
      (node (ref "S225") (pin "2") (pinfunction "2_2") (pintype "passive"))
      (node (ref "S239") (pin "2") (pinfunction "2_2") (pintype "passive"))
      (node (ref "S253") (pin "2") (pinfunction "2_2") (pintype "passive"))
      (node (ref "S263") (pin "2") (pinfunction "2_2") (pintype "passive"))
    )
    (net (code "13") (name "/col12") (class "Default")
      (node (ref "S212") (pin "2") (pinfunction "2_2") (pintype "passive"))
      (node (ref "S226") (pin "2") (pinfunction "2_2") (pintype "passive"))
      (node (ref "S240") (pin "2") (pinfunction "2_2") (pintype "passive"))
      (node (ref "S254") (pin "2") (pinfunction "2_2") (pintype "passive"))
      (node (ref "S264") (pin "1") (pinfunction "1_1") (pintype "passive"))
    )
    (net (code "14") (name "/col13") (class "Default")
      (node (ref "S213") (pin "2") (pinfunction "2_2") (pintype "passive"))
      (node (ref "S227") (pin "2") (pinfunction "2_2") (pintype "passive"))
      (node (ref "S241") (pin "2") (pinfunction "2_2") (pintype "passive"))
      (node (ref "S265") (pin "2") (pinfunction "2_2") (pintype "passive"))
      (node (ref "S267") (pin "1") (pinfunction "1_1") (pintype "passive"))
    )
    (net (code "15") (name "/col14") (class "Default")
      (node (ref "S214") (pin "2") (pinfunction "2_2") (pintype "passive"))
      (node (ref "S242") (pin "2") (pinfunction "2_2") (pintype "passive"))
    )
    (net (code "16") (name "/col15") (class "Default")
      (node (ref "S228") (pin "1") (pinfunction "1_1") (pintype "passive"))
      (node (ref "S255") (pin "2") (pinfunction "2_2") (pintype "passive"))
      (node (ref "S256") (pin "2") (pinfunction "2_2") (pintype "passive"))
      (node (ref "S266") (pin "2") (pinfunction "2_2") (pintype "passive"))
    )
    (net (code "17") (name "/row1") (class "Default")
      (node (ref "D201") (pin "2") (pinfunction "K_2") (pintype "passive"))
      (node (ref "D202") (pin "2") (pinfunction "K_2") (pintype "passive"))
      (node (ref "D203") (pin "2") (pinfunction "K_2") (pintype "passive"))
      (node (ref "D204") (pin "2") (pinfunction "K_2") (pintype "passive"))
      (node (ref "D205") (pin "2") (pinfunction "K_2") (pintype "passive"))
      (node (ref "D206") (pin "2") (pinfunction "K_2") (pintype "passive"))
      (node (ref "D207") (pin "2") (pinfunction "K_2") (pintype "passive"))
      (node (ref "D208") (pin "2") (pinfunction "K_2") (pintype "passive"))
      (node (ref "D209") (pin "2") (pinfunction "K_2") (pintype "passive"))
      (node (ref "D210") (pin "2") (pinfunction "K_2") (pintype "passive"))
      (node (ref "D211") (pin "2") (pinfunction "K_2") (pintype "passive"))
      (node (ref "D212") (pin "2") (pinfunction "K_2") (pintype "passive"))
      (node (ref "D213") (pin "2") (pinfunction "K_2") (pintype "passive"))
      (node (ref "D214") (pin "2") (pinfunction "K_2") (pintype "passive"))
      (node (ref "D228") (pin "2") (pinfunction "K_2") (pintype "passive"))
    )
    (net (code "18") (name "/row2") (class "Default")
      (node (ref "D215") (pin "2") (pinfunction "K_2") (pintype "passive"))
      (node (ref "D216") (pin "2") (pinfunction "K_2") (pintype "passive"))
      (node (ref "D217") (pin "2") (pinfunction "K_2") (pintype "passive"))
      (node (ref "D218") (pin "2") (pinfunction "K_2") (pintype "passive"))
      (node (ref "D219") (pin "2") (pinfunction "K_2") (pintype "passive"))
      (node (ref "D220") (pin "2") (pinfunction "K_2") (pintype "passive"))
      (node (ref "D221") (pin "2") (pinfunction "K_2") (pintype "passive"))
      (node (ref "D222") (pin "2") (pinfunction "K_2") (pintype "passive"))
      (node (ref "D223") (pin "2") (pinfunction "K_2") (pintype "passive"))
      (node (ref "D224") (pin "2") (pinfunction "K_2") (pintype "passive"))
      (node (ref "D225") (pin "2") (pinfunction "K_2") (pintype "passive"))
      (node (ref "D226") (pin "2") (pinfunction "K_2") (pintype "passive"))
      (node (ref "D227") (pin "2") (pinfunction "K_2") (pintype "passive"))
      (node (ref "D242") (pin "2") (pinfunction "K_2") (pintype "passive"))
      (node (ref "D268") (pin "2") (pinfunction "K_2") (pintype "passive"))
    )
    (net (code "19") (name "/row3") (class "Default")
      (node (ref "D229") (pin "2") (pinfunction "K_2") (pintype "passive"))
      (node (ref "D230") (pin "2") (pinfunction "K_2") (pintype "passive"))
      (node (ref "D231") (pin "2") (pinfunction "K_2") (pintype "passive"))
      (node (ref "D232") (pin "2") (pinfunction "K_2") (pintype "passive"))
      (node (ref "D233") (pin "2") (pinfunction "K_2") (pintype "passive"))
      (node (ref "D234") (pin "2") (pinfunction "K_2") (pintype "passive"))
      (node (ref "D235") (pin "2") (pinfunction "K_2") (pintype "passive"))
      (node (ref "D236") (pin "2") (pinfunction "K_2") (pintype "passive"))
      (node (ref "D237") (pin "2") (pinfunction "K_2") (pintype "passive"))
      (node (ref "D238") (pin "2") (pinfunction "K_2") (pintype "passive"))
      (node (ref "D239") (pin "2") (pinfunction "K_2") (pintype "passive"))
      (node (ref "D240") (pin "2") (pinfunction "K_2") (pintype "passive"))
      (node (ref "D241") (pin "2") (pinfunction "K_2") (pintype "passive"))
      (node (ref "D256") (pin "2") (pinfunction "K_2") (pintype "passive"))
    )
    (net (code "20") (name "/row4") (class "Default")
      (node (ref "D243") (pin "2") (pinfunction "K_2") (pintype "passive"))
      (node (ref "D244") (pin "2") (pinfunction "K_2") (pintype "passive"))
      (node (ref "D245") (pin "2") (pinfunction "K_2") (pintype "passive"))
      (node (ref "D246") (pin "2") (pinfunction "K_2") (pintype "passive"))
      (node (ref "D247") (pin "2") (pinfunction "K_2") (pintype "passive"))
      (node (ref "D248") (pin "2") (pinfunction "K_2") (pintype "passive"))
      (node (ref "D249") (pin "2") (pinfunction "K_2") (pintype "passive"))
      (node (ref "D250") (pin "2") (pinfunction "K_2") (pintype "passive"))
      (node (ref "D251") (pin "2") (pinfunction "K_2") (pintype "passive"))
      (node (ref "D252") (pin "2") (pinfunction "K_2") (pintype "passive"))
      (node (ref "D253") (pin "2") (pinfunction "K_2") (pintype "passive"))
      (node (ref "D254") (pin "2") (pinfunction "K_2") (pintype "passive"))
      (node (ref "D255") (pin "2") (pinfunction "K_2") (pintype "passive"))
      (node (ref "D267") (pin "2") (pinfunction "K_2") (pintype "passive"))
    )
    (net (code "21") (name "/row5") (class "Default")
      (node (ref "D257") (pin "2") (pinfunction "K_2") (pintype "passive"))
      (node (ref "D258") (pin "2") (pinfunction "K_2") (pintype "passive"))
      (node (ref "D259") (pin "2") (pinfunction "K_2") (pintype "passive"))
      (node (ref "D260") (pin "2") (pinfunction "K_2") (pintype "passive"))
      (node (ref "D261") (pin "2") (pinfunction "K_2") (pintype "passive"))
      (node (ref "D262") (pin "2") (pinfunction "K_2") (pintype "passive"))
      (node (ref "D263") (pin "2") (pinfunction "K_2") (pintype "passive"))
      (node (ref "D264") (pin "2") (pinfunction "K_2") (pintype "passive"))
      (node (ref "D265") (pin "2") (pinfunction "K_2") (pintype "passive"))
      (node (ref "D266") (pin "2") (pinfunction "K_2") (pintype "passive"))
    )
    (net (code "22") (name "Net-(D201-A)") (class "Default")
      (node (ref "D201") (pin "1") (pinfunction "A_1") (pintype "passive"))
      (node (ref "S201") (pin "1") (pinfunction "1_1") (pintype "passive"))
    )
    (net (code "23") (name "Net-(D202-A)") (class "Default")
      (node (ref "D202") (pin "1") (pinfunction "A_1") (pintype "passive"))
      (node (ref "S202") (pin "1") (pinfunction "1_1") (pintype "passive"))
    )
    (net (code "24") (name "Net-(D203-A)") (class "Default")
      (node (ref "D203") (pin "1") (pinfunction "A_1") (pintype "passive"))
      (node (ref "S203") (pin "1") (pinfunction "1_1") (pintype "passive"))
    )
    (net (code "25") (name "Net-(D204-A)") (class "Default")
      (node (ref "D204") (pin "1") (pinfunction "A_1") (pintype "passive"))
      (node (ref "S204") (pin "1") (pinfunction "1_1") (pintype "passive"))
    )
    (net (code "26") (name "Net-(D205-A)") (class "Default")
      (node (ref "D205") (pin "1") (pinfunction "A_1") (pintype "passive"))
      (node (ref "S205") (pin "1") (pinfunction "1_1") (pintype "passive"))
    )
    (net (code "27") (name "Net-(D206-A)") (class "Default")
      (node (ref "D206") (pin "1") (pinfunction "A_1") (pintype "passive"))
      (node (ref "S206") (pin "1") (pinfunction "1_1") (pintype "passive"))
    )
    (net (code "28") (name "Net-(D207-A)") (class "Default")
      (node (ref "D207") (pin "1") (pinfunction "A_1") (pintype "passive"))
      (node (ref "S207") (pin "1") (pinfunction "1_1") (pintype "passive"))
    )
    (net (code "29") (name "Net-(D208-A)") (class "Default")
      (node (ref "D208") (pin "1") (pinfunction "A_1") (pintype "passive"))
      (node (ref "S208") (pin "1") (pinfunction "1_1") (pintype "passive"))
    )
    (net (code "30") (name "Net-(D209-A)") (class "Default")
      (node (ref "D209") (pin "1") (pinfunction "A_1") (pintype "passive"))
      (node (ref "S209") (pin "1") (pinfunction "1_1") (pintype "passive"))
    )
    (net (code "31") (name "Net-(D210-A)") (class "Default")
      (node (ref "D210") (pin "1") (pinfunction "A_1") (pintype "passive"))
      (node (ref "S210") (pin "1") (pinfunction "1_1") (pintype "passive"))
    )
    (net (code "32") (name "Net-(D211-A)") (class "Default")
      (node (ref "D211") (pin "1") (pinfunction "A_1") (pintype "passive"))
      (node (ref "S211") (pin "1") (pinfunction "1_1") (pintype "passive"))
    )
    (net (code "33") (name "Net-(D212-A)") (class "Default")
      (node (ref "D212") (pin "1") (pinfunction "A_1") (pintype "passive"))
      (node (ref "S212") (pin "1") (pinfunction "1_1") (pintype "passive"))
    )
    (net (code "34") (name "Net-(D213-A)") (class "Default")
      (node (ref "D213") (pin "1") (pinfunction "A_1") (pintype "passive"))
      (node (ref "S213") (pin "1") (pinfunction "1_1") (pintype "passive"))
    )
    (net (code "35") (name "Net-(D214-A)") (class "Default")
      (node (ref "D214") (pin "1") (pinfunction "A_1") (pintype "passive"))
      (node (ref "S214") (pin "1") (pinfunction "1_1") (pintype "passive"))
    )
    (net (code "36") (name "Net-(D215-A)") (class "Default")
      (node (ref "D215") (pin "1") (pinfunction "A_1") (pintype "passive"))
      (node (ref "S215") (pin "2") (pinfunction "2_2") (pintype "passive"))
    )
    (net (code "37") (name "Net-(D216-A)") (class "Default")
      (node (ref "D216") (pin "1") (pinfunction "A_1") (pintype "passive"))
      (node (ref "S216") (pin "1") (pinfunction "1_1") (pintype "passive"))
    )
    (net (code "38") (name "Net-(D217-A)") (class "Default")
      (node (ref "D217") (pin "1") (pinfunction "A_1") (pintype "passive"))
      (node (ref "S217") (pin "1") (pinfunction "1_1") (pintype "passive"))
    )
    (net (code "39") (name "Net-(D218-A)") (class "Default")
      (node (ref "D218") (pin "1") (pinfunction "A_1") (pintype "passive"))
      (node (ref "S218") (pin "1") (pinfunction "1_1") (pintype "passive"))
    )
    (net (code "40") (name "Net-(D219-A)") (class "Default")
      (node (ref "D219") (pin "1") (pinfunction "A_1") (pintype "passive"))
      (node (ref "S219") (pin "1") (pinfunction "1_1") (pintype "passive"))
    )
    (net (code "41") (name "Net-(D220-A)") (class "Default")
      (node (ref "D220") (pin "1") (pinfunction "A_1") (pintype "passive"))
      (node (ref "S220") (pin "1") (pinfunction "1_1") (pintype "passive"))
    )
    (net (code "42") (name "Net-(D221-A)") (class "Default")
      (node (ref "D221") (pin "1") (pinfunction "A_1") (pintype "passive"))
      (node (ref "S221") (pin "1") (pinfunction "1_1") (pintype "passive"))
    )
    (net (code "43") (name "Net-(D222-A)") (class "Default")
      (node (ref "D222") (pin "1") (pinfunction "A_1") (pintype "passive"))
      (node (ref "S222") (pin "1") (pinfunction "1_1") (pintype "passive"))
    )
    (net (code "44") (name "Net-(D223-A)") (class "Default")
      (node (ref "D223") (pin "1") (pinfunction "A_1") (pintype "passive"))
      (node (ref "S223") (pin "1") (pinfunction "1_1") (pintype "passive"))
    )
    (net (code "45") (name "Net-(D224-A)") (class "Default")
      (node (ref "D224") (pin "1") (pinfunction "A_1") (pintype "passive"))
      (node (ref "S224") (pin "1") (pinfunction "1_1") (pintype "passive"))
    )
    (net (code "46") (name "Net-(D225-A)") (class "Default")
      (node (ref "D225") (pin "1") (pinfunction "A_1") (pintype "passive"))
      (node (ref "S225") (pin "1") (pinfunction "1_1") (pintype "passive"))
    )
    (net (code "47") (name "Net-(D226-A)") (class "Default")
      (node (ref "D226") (pin "1") (pinfunction "A_1") (pintype "passive"))
      (node (ref "S226") (pin "1") (pinfunction "1_1") (pintype "passive"))
    )
    (net (code "48") (name "Net-(D227-A)") (class "Default")
      (node (ref "D227") (pin "1") (pinfunction "A_1") (pintype "passive"))
      (node (ref "S227") (pin "1") (pinfunction "1_1") (pintype "passive"))
    )
    (net (code "49") (name "Net-(D228-A)") (class "Default")
      (node (ref "D228") (pin "1") (pinfunction "A_1") (pintype "passive"))
      (node (ref "S228") (pin "2") (pinfunction "2_2") (pintype "passive"))
    )
    (net (code "50") (name "Net-(D229-A)") (class "Default")
      (node (ref "D229") (pin "1") (pinfunction "A_1") (pintype "passive"))
      (node (ref "S229") (pin "1") (pinfunction "1_1") (pintype "passive"))
    )
    (net (code "51") (name "Net-(D230-A)") (class "Default")
      (node (ref "D230") (pin "1") (pinfunction "A_1") (pintype "passive"))
      (node (ref "S230") (pin "1") (pinfunction "1_1") (pintype "passive"))
    )
    (net (code "52") (name "Net-(D231-A)") (class "Default")
      (node (ref "D231") (pin "1") (pinfunction "A_1") (pintype "passive"))
      (node (ref "S231") (pin "1") (pinfunction "1_1") (pintype "passive"))
    )
    (net (code "53") (name "Net-(D232-A)") (class "Default")
      (node (ref "D232") (pin "1") (pinfunction "A_1") (pintype "passive"))
      (node (ref "S232") (pin "1") (pinfunction "1_1") (pintype "passive"))
    )
    (net (code "54") (name "Net-(D233-A)") (class "Default")
      (node (ref "D233") (pin "1") (pinfunction "A_1") (pintype "passive"))
      (node (ref "S233") (pin "1") (pinfunction "1_1") (pintype "passive"))
    )
    (net (code "55") (name "Net-(D234-A)") (class "Default")
      (node (ref "D234") (pin "1") (pinfunction "A_1") (pintype "passive"))
      (node (ref "S234") (pin "1") (pinfunction "1_1") (pintype "passive"))
    )
    (net (code "56") (name "Net-(D235-A)") (class "Default")
      (node (ref "D235") (pin "1") (pinfunction "A_1") (pintype "passive"))
      (node (ref "S235") (pin "1") (pinfunction "1_1") (pintype "passive"))
    )
    (net (code "57") (name "Net-(D236-A)") (class "Default")
      (node (ref "D236") (pin "1") (pinfunction "A_1") (pintype "passive"))
      (node (ref "S236") (pin "1") (pinfunction "1_1") (pintype "passive"))
    )
    (net (code "58") (name "Net-(D237-A)") (class "Default")
      (node (ref "D237") (pin "1") (pinfunction "A_1") (pintype "passive"))
      (node (ref "S237") (pin "1") (pinfunction "1_1") (pintype "passive"))
    )
    (net (code "59") (name "Net-(D238-A)") (class "Default")
      (node (ref "D238") (pin "1") (pinfunction "A_1") (pintype "passive"))
      (node (ref "S238") (pin "1") (pinfunction "1_1") (pintype "passive"))
    )
    (net (code "60") (name "Net-(D239-A)") (class "Default")
      (node (ref "D239") (pin "1") (pinfunction "A_1") (pintype "passive"))
      (node (ref "S239") (pin "1") (pinfunction "1_1") (pintype "passive"))
    )
    (net (code "61") (name "Net-(D240-A)") (class "Default")
      (node (ref "D240") (pin "1") (pinfunction "A_1") (pintype "passive"))
      (node (ref "S240") (pin "1") (pinfunction "1_1") (pintype "passive"))
    )
    (net (code "62") (name "Net-(D241-A)") (class "Default")
      (node (ref "D241") (pin "1") (pinfunction "A_1") (pintype "passive"))
      (node (ref "S241") (pin "1") (pinfunction "1_1") (pintype "passive"))
    )
    (net (code "63") (name "Net-(D242-A)") (class "Default")
      (node (ref "D242") (pin "1") (pinfunction "A_1") (pintype "passive"))
      (node (ref "S242") (pin "1") (pinfunction "1_1") (pintype "passive"))
    )
    (net (code "64") (name "Net-(D243-A)") (class "Default")
      (node (ref "D243") (pin "1") (pinfunction "A_1") (pintype "passive"))
      (node (ref "S243") (pin "1") (pinfunction "1_1") (pintype "passive"))
    )
    (net (code "65") (name "Net-(D244-A)") (class "Default")
      (node (ref "D244") (pin "1") (pinfunction "A_1") (pintype "passive"))
      (node (ref "S244") (pin "1") (pinfunction "1_1") (pintype "passive"))
    )
    (net (code "66") (name "Net-(D245-A)") (class "Default")
      (node (ref "D245") (pin "1") (pinfunction "A_1") (pintype "passive"))
      (node (ref "S245") (pin "1") (pinfunction "1_1") (pintype "passive"))
    )
    (net (code "67") (name "Net-(D246-A)") (class "Default")
      (node (ref "D246") (pin "1") (pinfunction "A_1") (pintype "passive"))
      (node (ref "S246") (pin "1") (pinfunction "1_1") (pintype "passive"))
    )
    (net (code "68") (name "Net-(D247-A)") (class "Default")
      (node (ref "D247") (pin "1") (pinfunction "A_1") (pintype "passive"))
      (node (ref "S247") (pin "1") (pinfunction "1_1") (pintype "passive"))
    )
    (net (code "69") (name "Net-(D248-A)") (class "Default")
      (node (ref "D248") (pin "1") (pinfunction "A_1") (pintype "passive"))
      (node (ref "S248") (pin "1") (pinfunction "1_1") (pintype "passive"))
    )
    (net (code "70") (name "Net-(D249-A)") (class "Default")
      (node (ref "D249") (pin "1") (pinfunction "A_1") (pintype "passive"))
      (node (ref "S249") (pin "1") (pinfunction "1_1") (pintype "passive"))
    )
    (net (code "71") (name "Net-(D250-A)") (class "Default")
      (node (ref "D250") (pin "1") (pinfunction "A_1") (pintype "passive"))
      (node (ref "S250") (pin "1") (pinfunction "1_1") (pintype "passive"))
    )
    (net (code "72") (name "Net-(D251-A)") (class "Default")
      (node (ref "D251") (pin "1") (pinfunction "A_1") (pintype "passive"))
      (node (ref "S251") (pin "1") (pinfunction "1_1") (pintype "passive"))
    )
    (net (code "73") (name "Net-(D252-A)") (class "Default")
      (node (ref "D252") (pin "1") (pinfunction "A_1") (pintype "passive"))
      (node (ref "S252") (pin "1") (pinfunction "1_1") (pintype "passive"))
    )
    (net (code "74") (name "Net-(D253-A)") (class "Default")
      (node (ref "D253") (pin "1") (pinfunction "A_1") (pintype "passive"))
      (node (ref "S253") (pin "1") (pinfunction "1_1") (pintype "passive"))
    )
    (net (code "75") (name "Net-(D254-A)") (class "Default")
      (node (ref "D254") (pin "1") (pinfunction "A_1") (pintype "passive"))
      (node (ref "S254") (pin "1") (pinfunction "1_1") (pintype "passive"))
    )
    (net (code "76") (name "Net-(D255-A)") (class "Default")
      (node (ref "D255") (pin "1") (pinfunction "A_1") (pintype "passive"))
      (node (ref "S255") (pin "1") (pinfunction "1_1") (pintype "passive"))
    )
    (net (code "77") (name "Net-(D256-A)") (class "Default")
      (node (ref "D256") (pin "1") (pinfunction "A_1") (pintype "passive"))
      (node (ref "S256") (pin "1") (pinfunction "1_1") (pintype "passive"))
    )
    (net (code "78") (name "Net-(D257-A)") (class "Default")
      (node (ref "D257") (pin "1") (pinfunction "A_1") (pintype "passive"))
      (node (ref "S257") (pin "2") (pinfunction "2_2") (pintype "passive"))
    )
    (net (code "79") (name "Net-(D258-A)") (class "Default")
      (node (ref "D258") (pin "1") (pinfunction "A_1") (pintype "passive"))
      (node (ref "S258") (pin "1") (pinfunction "1_1") (pintype "passive"))
    )
    (net (code "80") (name "Net-(D259-A)") (class "Default")
      (node (ref "D259") (pin "1") (pinfunction "A_1") (pintype "passive"))
      (node (ref "S259") (pin "1") (pinfunction "1_1") (pintype "passive"))
    )
    (net (code "81") (name "Net-(D260-A)") (class "Default")
      (node (ref "D260") (pin "1") (pinfunction "A_1") (pintype "passive"))
      (node (ref "S260") (pin "1") (pinfunction "1_1") (pintype "passive"))
    )
    (net (code "82") (name "Net-(D261-A)") (class "Default")
      (node (ref "D261") (pin "1") (pinfunction "A_1") (pintype "passive"))
      (node (ref "S261") (pin "1") (pinfunction "1_1") (pintype "passive"))
    )
    (net (code "83") (name "Net-(D262-A)") (class "Default")
      (node (ref "D262") (pin "1") (pinfunction "A_1") (pintype "passive"))
      (node (ref "S262") (pin "1") (pinfunction "1_1") (pintype "passive"))
    )
    (net (code "84") (name "Net-(D263-A)") (class "Default")
      (node (ref "D263") (pin "1") (pinfunction "A_1") (pintype "passive"))
      (node (ref "S263") (pin "1") (pinfunction "1_1") (pintype "passive"))
    )
    (net (code "85") (name "Net-(D264-A)") (class "Default")
      (node (ref "D264") (pin "1") (pinfunction "A_1") (pintype "passive"))
      (node (ref "S264") (pin "2") (pinfunction "2_2") (pintype "passive"))
    )
    (net (code "86") (name "Net-(D265-A)") (class "Default")
      (node (ref "D265") (pin "1") (pinfunction "A_1") (pintype "passive"))
      (node (ref "S265") (pin "1") (pinfunction "1_1") (pintype "passive"))
    )
    (net (code "87") (name "Net-(D266-A)") (class "Default")
      (node (ref "D266") (pin "1") (pinfunction "A_1") (pintype "passive"))
      (node (ref "S266") (pin "1") (pinfunction "1_1") (pintype "passive"))
    )
    (net (code "88") (name "Net-(D267-A)") (class "Default")
      (node (ref "D267") (pin "1") (pinfunction "A_1") (pintype "passive"))
      (node (ref "S267") (pin "2") (pinfunction "2_2") (pintype "passive"))
    )
  )
)
